# Socket-board.net
KiCad netlist of a schematic drawn in Altium Designer
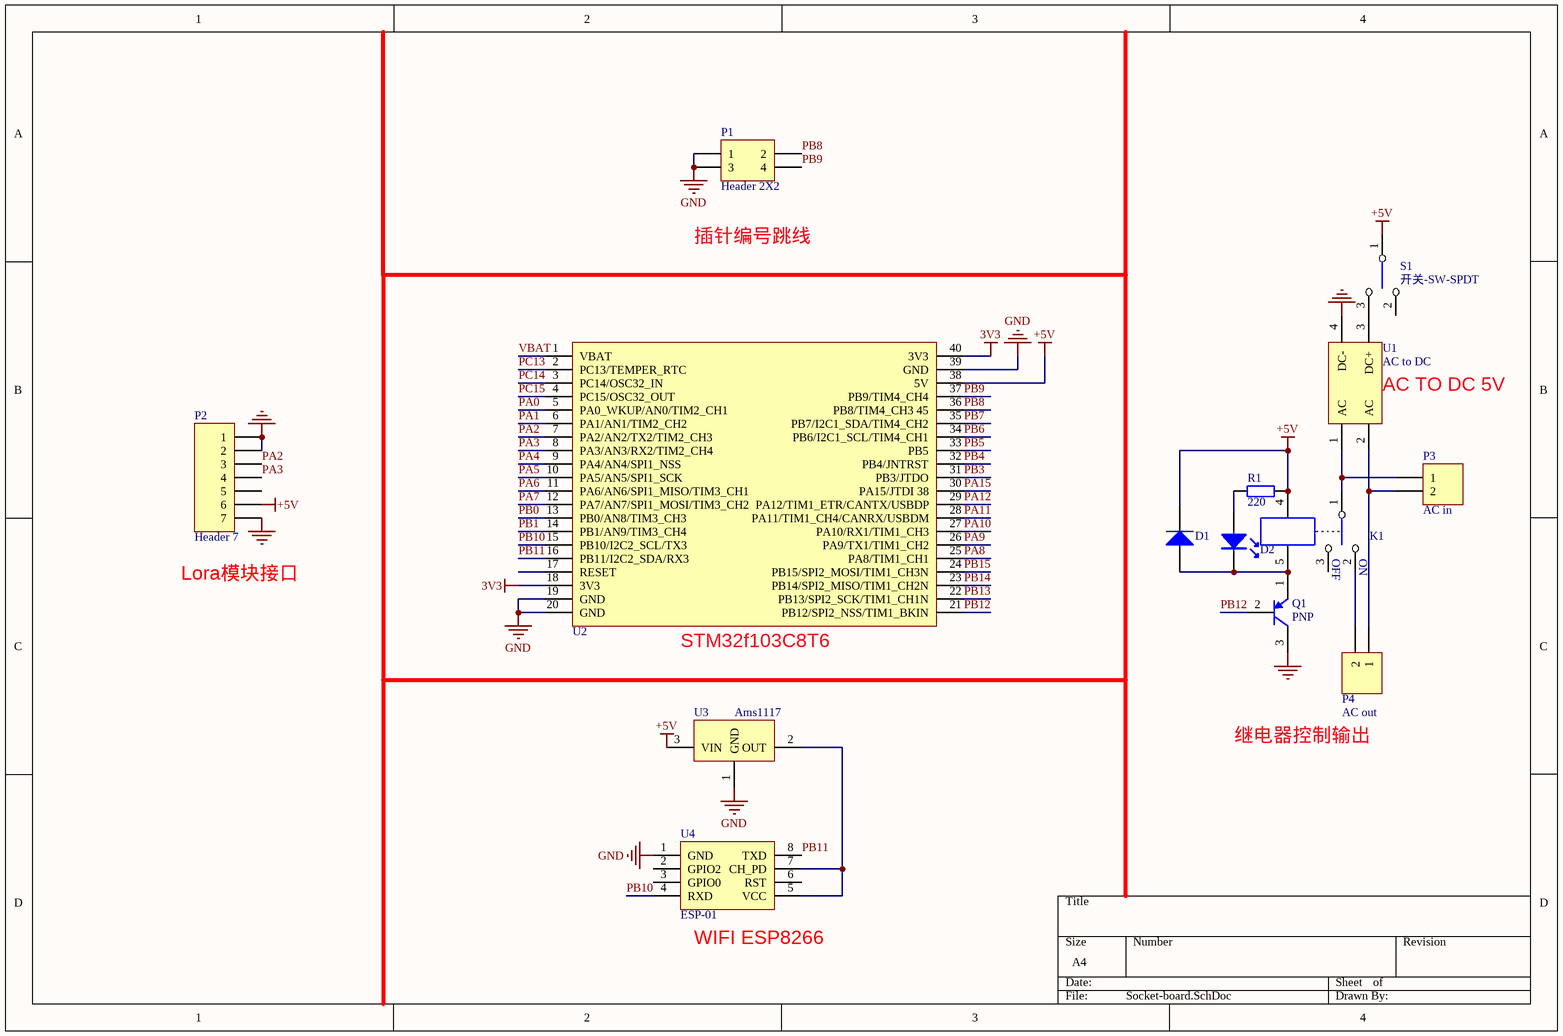
[diagram p0: Socket-board.SchDoc]

(export (version "E")
  (design (tool "Eeschema 10.0.6"))
  (components
    (comp (ref "D1")
      (value "Diode 1N4001")
      (footprint "DO-41")
      (description "1 Amp General Purpose Rectifier")
      (fields (field (name "PUBLISHER") "Altium Limited"))
      (libsource (lib "Miscellaneous Devices") (part "Diode 1N4001"))
    )
    (comp (ref "D2") (value "二极管--发光") (footprint "LED-5") (libsource (lib "买鹏飞的库") (part "二极管--发光")))
    (comp (ref "K1") (value "继电器-RELAY-3") (footprint "继电器5") (libsource (lib "*") (part "继电器-RELAY-3")))
    (comp (ref "P1")
      (value "Header 2X2")
      (footprint "HDR2X2")
      (description "Header, 2-Pin, Dual row")
      (fields (field (name "PUBLISHER") "Altium Limited"))
      (libsource (lib "Miscellaneous Connectors") (part "Header 2X2"))
    )
    (comp (ref "P2")
      (value "Header 7")
      (footprint "PE32(433T20DC)")
      (description "Header, 7-Pin")
      (fields (field (name "PUBLISHER") "Altium Limited"))
      (libsource (lib "Miscellaneous Connectors") (part "Header 7"))
    )
    (comp (ref "P3")
      (value "AC in")
      (footprint "KF7.62-2P")
      (description "Header, 2-Pin")
      (fields (field (name "PUBLISHER") "Altium Limited"))
      (libsource (lib "") (part "Header 2_1"))
    )
    (comp (ref "P4")
      (value "AC out")
      (footprint "KF7.62-2P")
      (description "Header, 2-Pin")
      (fields (field (name "PUBLISHER") "Altium Limited"))
      (libsource (lib "Miscellaneous Connectors") (part "Header 2"))
    )
    (comp (ref "Q1") (value "PNP") (footprint "TO-92B") (libsource (lib "买鹏飞的库") (part "三极管-PNP")))
    (comp (ref "R1")
      (value "220")
      (footprint "AXIAL-0.4")
      (description "Resistor")
      (fields (field (name "Comment") "Res2") (field (name "PUBLISHER") "Altium Limited"))
      (libsource (lib "Miscellaneous Devices") (part "Res2"))
    )
    (comp (ref "S1") (value "开关-SW-SPDT") (footprint "SW3") (libsource (lib "买鹏飞的库") (part "开关-SW-SPDT")))
    (comp (ref "U1")
      (value "AC to DC")
      (footprint "艾尔塞VIPer12A")
      (libsource (lib "买鹏飞的库") (part "艾尔塞VIPer12A"))
    )
    (comp (ref "U2")
      (value "Core_STM32_YX")
      (footprint "Core_STM32_YX")
      (libsource (lib "买鹏飞的库") (part "Core_STM32_YX"))
    )
    (comp (ref "U3") (value "Ams1117") (footprint "sot-223") (libsource (lib "买鹏飞的库") (part "芯片-AMS1117")))
    (comp (ref "U4")
      (value "ESP-01")
      (footprint "模块ESP8266")
      (libsource (lib "买鹏飞的库") (part "模块ESP8266 ESP-01"))
    )
  )
  (nets
    (net (code "1") (name "+5V") (class "Default")
      (node (ref "D1") (pin "2") (pinfunction "K_2") (pintype "passive"))
      (node (ref "K1") (pin "4") (pinfunction "4_4") (pintype "passive"))
      (node (ref "P2") (pin "6") (pinfunction "6_6") (pintype "passive"))
      (node (ref "R1") (pin "1") (pinfunction "1_1") (pintype "passive"))
      (node (ref "S1") (pin "1") (pinfunction "1_1") (pintype "passive"))
      (node (ref "U2") (pin "38") (pinfunction "5V_38") (pintype "passive"))
      (node (ref "U3") (pin "3") (pinfunction "VIN_3") (pintype "passive"))
    )
    (net (code "2") (name "/PA0") (class "Default")
      (node (ref "U2") (pin "5") (pinfunction "PA0_WKUP/AN0/TIM2_CH1_5") (pintype "passive"))
    )
    (net (code "3") (name "/PA1") (class "Default")
      (node (ref "U2") (pin "6") (pinfunction "PA1/AN1/TIM2_CH2_6") (pintype "passive"))
    )
    (net (code "4") (name "/PA2") (class "Default")
      (node (ref "P2") (pin "3") (pinfunction "3_3") (pintype "passive"))
      (node (ref "U2") (pin "7") (pinfunction "PA2/AN2/TX2/TIM2_CH3_7") (pintype "passive"))
    )
    (net (code "5") (name "/PA3") (class "Default")
      (node (ref "P2") (pin "4") (pinfunction "4_4") (pintype "passive"))
      (node (ref "U2") (pin "8") (pinfunction "PA3/AN3/RX2/TIM2_CH4_8") (pintype "passive"))
    )
    (net (code "6") (name "/PA4") (class "Default")
      (node (ref "U2") (pin "9") (pinfunction "PA4/AN4/SPI1_NSS_9") (pintype "passive"))
    )
    (net (code "7") (name "/PA5") (class "Default")
      (node (ref "U2") (pin "10") (pinfunction "PA5/AN5/SPI1_SCK_10") (pintype "passive"))
    )
    (net (code "8") (name "/PA6") (class "Default")
      (node (ref "U2") (pin "11") (pinfunction "PA6/AN6/SPI1_MISO/TIM3_CH1_11") (pintype "passive"))
    )
    (net (code "9") (name "/PA7") (class "Default")
      (node (ref "U2") (pin "12") (pinfunction "PA7/AN7/SPI1_MOSI/TIM3_CH2_12") (pintype "passive"))
    )
    (net (code "10") (name "/PA8") (class "Default")
      (node (ref "U2") (pin "25") (pinfunction "PA8/TIM1_CH1_25") (pintype "passive"))
    )
    (net (code "11") (name "/PA9") (class "Default")
      (node (ref "U2") (pin "26") (pinfunction "PA9/TX1/TIM1_CH2_26") (pintype "passive"))
    )
    (net (code "12") (name "/PA10") (class "Default")
      (node (ref "U2") (pin "27") (pinfunction "PA10/RX1/TIM1_CH3_27") (pintype "passive"))
    )
    (net (code "13") (name "/PA11") (class "Default")
      (node (ref "U2") (pin "28") (pinfunction "PA11/TIM1_CH4/CANRX/USBDM_28") (pintype "passive"))
    )
    (net (code "14") (name "/PA12") (class "Default")
      (node (ref "U2") (pin "29") (pinfunction "PA12/TIM1_ETR/CANTX/USBDP_29") (pintype "passive"))
    )
    (net (code "15") (name "/PA15") (class "Default")
      (node (ref "U2") (pin "30") (pinfunction "PA15/JTDI_38_30") (pintype "passive"))
    )
    (net (code "16") (name "/PB0") (class "Default")
      (node (ref "U2") (pin "13") (pinfunction "PB0/AN8/TIM3_CH3_13") (pintype "passive"))
    )
    (net (code "17") (name "/PB1") (class "Default")
      (node (ref "U2") (pin "14") (pinfunction "PB1/AN9/TIM3_CH4_14") (pintype "passive"))
    )
    (net (code "18") (name "/PB3") (class "Default")
      (node (ref "U2") (pin "31") (pinfunction "PB3/JTDO_31") (pintype "passive"))
    )
    (net (code "19") (name "/PB4") (class "Default")
      (node (ref "U2") (pin "32") (pinfunction "PB4/JNTRST_32") (pintype "passive"))
    )
    (net (code "20") (name "/PB5") (class "Default")
      (node (ref "U2") (pin "33") (pinfunction "PB5_33") (pintype "passive"))
    )
    (net (code "21") (name "/PB6") (class "Default")
      (node (ref "U2") (pin "34") (pinfunction "PB6/I2C1_SCL/TIM4_CH1_34") (pintype "passive"))
    )
    (net (code "22") (name "/PB7") (class "Default")
      (node (ref "U2") (pin "35") (pinfunction "PB7/I2C1_SDA/TIM4_CH2_35") (pintype "passive"))
    )
    (net (code "23") (name "/PB8") (class "Default")
      (node (ref "P1") (pin "2") (pinfunction "2_2") (pintype "passive"))
      (node (ref "U2") (pin "36") (pinfunction "PB8/TIM4_CH3_45_36") (pintype "passive"))
    )
    (net (code "24") (name "/PB9") (class "Default")
      (node (ref "P1") (pin "4") (pinfunction "4_4") (pintype "passive"))
      (node (ref "U2") (pin "37") (pinfunction "PB9/TIM4_CH4_37") (pintype "passive"))
    )
    (net (code "25") (name "/PB10") (class "Default")
      (node (ref "U2") (pin "15") (pinfunction "PB10/I2C2_SCL/TX3_15") (pintype "passive"))
      (node (ref "U4") (pin "4") (pinfunction "RXD_4") (pintype "power_in"))
    )
    (net (code "26") (name "/PB11") (class "Default")
      (node (ref "U2") (pin "16") (pinfunction "PB11/I2C2_SDA/RX3_16") (pintype "passive"))
      (node (ref "U4") (pin "8") (pinfunction "TXD_8") (pintype "power_in"))
    )
    (net (code "27") (name "/PB12") (class "Default")
      (node (ref "Q1") (pin "2") (pinfunction "B_2") (pintype "passive"))
      (node (ref "U2") (pin "21") (pinfunction "PB12/SPI2_NSS/TIM1_BKIN_21") (pintype "passive"))
    )
    (net (code "28") (name "/PB13") (class "Default")
      (node (ref "U2") (pin "22") (pinfunction "PB13/SPI2_SCK/TIM1_CH1N_22") (pintype "passive"))
    )
    (net (code "29") (name "/PB14") (class "Default")
      (node (ref "U2") (pin "23") (pinfunction "PB14/SPI2_MISO/TIM1_CH2N_23") (pintype "passive"))
    )
    (net (code "30") (name "/PB15") (class "Default")
      (node (ref "U2") (pin "24") (pinfunction "PB15/SPI2_MOSI/TIM1_CH3N_24") (pintype "passive"))
    )
    (net (code "31") (name "/PC13") (class "Default")
      (node (ref "U2") (pin "2") (pinfunction "PC13/TEMPER_RTC_2") (pintype "passive"))
    )
    (net (code "32") (name "/PC14") (class "Default")
      (node (ref "U2") (pin "3") (pinfunction "PC14/OSC32_IN_3") (pintype "passive"))
    )
    (net (code "33") (name "/PC15") (class "Default")
      (node (ref "U2") (pin "4") (pinfunction "PC15/OSC32_OUT_4") (pintype "passive"))
    )
    (net (code "34") (name "/VBAT") (class "Default")
      (node (ref "U2") (pin "1") (pinfunction "VBAT_1") (pintype "passive"))
    )
    (net (code "35") (name "3V3") (class "Default")
      (node (ref "U2") (pin "18") (pinfunction "3V3_18") (pintype "passive"))
      (node (ref "U2") (pin "40") (pinfunction "3V3_40") (pintype "passive"))
    )
    (net (code "36") (name "GND") (class "Default")
      (node (ref "P1") (pin "1") (pinfunction "1_1") (pintype "passive"))
      (node (ref "P1") (pin "3") (pinfunction "3_3") (pintype "passive"))
      (node (ref "P2") (pin "1") (pinfunction "1_1") (pintype "passive"))
      (node (ref "P2") (pin "2") (pinfunction "2_2") (pintype "passive"))
      (node (ref "P2") (pin "7") (pinfunction "7_7") (pintype "passive"))
      (node (ref "Q1") (pin "3") (pinfunction "C_3") (pintype "passive"))
      (node (ref "U1") (pin "4") (pinfunction "DC-_4") (pintype "passive"))
      (node (ref "U2") (pin "19") (pinfunction "GND_19") (pintype "passive"))
      (node (ref "U2") (pin "20") (pinfunction "GND_20") (pintype "passive"))
      (node (ref "U2") (pin "39") (pinfunction "GND_39") (pintype "passive"))
      (node (ref "U3") (pin "1") (pinfunction "GND_1") (pintype "passive"))
      (node (ref "U4") (pin "1") (pinfunction "GND_1") (pintype "power_in"))
    )
    (net (code "37") (name "Net-(D1-A)") (class "Default")
      (node (ref "D1") (pin "1") (pinfunction "A_1") (pintype "passive"))
      (node (ref "D2") (pin "2") (pinfunction "2_2") (pintype "passive"))
      (node (ref "K1") (pin "5") (pinfunction "5_5") (pintype "passive"))
      (node (ref "Q1") (pin "1") (pinfunction "E_1") (pintype "passive"))
    )
    (net (code "38") (name "Net-(D2-Pad1)") (class "Default")
      (node (ref "D2") (pin "1") (pinfunction "1_1") (pintype "passive"))
      (node (ref "R1") (pin "2") (pinfunction "2_2") (pintype "passive"))
    )
    (net (code "39") (name "Net-(K1-Pad1)") (class "Default")
      (node (ref "K1") (pin "1") (pinfunction "1_1") (pintype "passive"))
      (node (ref "P3") (pin "1") (pinfunction "1_1") (pintype "passive"))
      (node (ref "U1") (pin "1") (pinfunction "AC_1") (pintype "passive"))
    )
    (net (code "40") (name "Net-(K1-Pad2)") (class "Default")
      (node (ref "K1") (pin "2") (pinfunction "2_2") (pintype "passive"))
      (node (ref "P4") (pin "2") (pinfunction "2_2") (pintype "passive"))
    )
    (net (code "41") (name "Net-(P3-Pad2)") (class "Default")
      (node (ref "P3") (pin "2") (pinfunction "2_2") (pintype "passive"))
      (node (ref "P4") (pin "1") (pinfunction "1_1") (pintype "passive"))
      (node (ref "U1") (pin "2") (pinfunction "AC_2") (pintype "passive"))
    )
    (net (code "42") (name "Net-(U1-DC+)") (class "Default")
      (node (ref "S1") (pin "3") (pinfunction "3_3") (pintype "passive"))
      (node (ref "U1") (pin "3") (pinfunction "DC+_3") (pintype "passive"))
    )
    (net (code "43") (name "Net-(U3-OUT)") (class "Default")
      (node (ref "U3") (pin "2") (pinfunction "OUT_2") (pintype "passive"))
      (node (ref "U4") (pin "5") (pinfunction "VCC_5") (pintype "power_in"))
      (node (ref "U4") (pin "7") (pinfunction "CH_PD_7") (pintype "power_in"))
    )
    (net (code "44") (name "unconnected-(K1-Pad3)") (class "Default")
      (node (ref "K1") (pin "3") (pinfunction "3_3") (pintype "passive"))
    )
    (net (code "45") (name "unconnected-(P2-Pad5)") (class "Default")
      (node (ref "P2") (pin "5") (pinfunction "5_5") (pintype "passive"))
    )
    (net (code "46") (name "unconnected-(S1-Pad2)") (class "Default")
      (node (ref "S1") (pin "2") (pinfunction "2_2") (pintype "passive"))
    )
    (net (code "47") (name "unconnected-(U2-RESET-Pad17)") (class "Default")
      (node (ref "U2") (pin "17") (pinfunction "RESET_17") (pintype "passive"))
    )
    (net (code "48") (name "unconnected-(U4-GPIO0-Pad3)") (class "Default")
      (node (ref "U4") (pin "3") (pinfunction "GPIO0_3") (pintype "power_in"))
    )
    (net (code "49") (name "unconnected-(U4-GPIO2-Pad2)") (class "Default")
      (node (ref "U4") (pin "2") (pinfunction "GPIO2_2") (pintype "power_in"))
    )
    (net (code "50") (name "unconnected-(U4-RST-Pad6)") (class "Default")
      (node (ref "U4") (pin "6") (pinfunction "RST_6") (pintype "power_in"))
    )
  )
)
